# Power_and_Clocks.net
KiCad netlist of a schematic drawn in Altium Designer
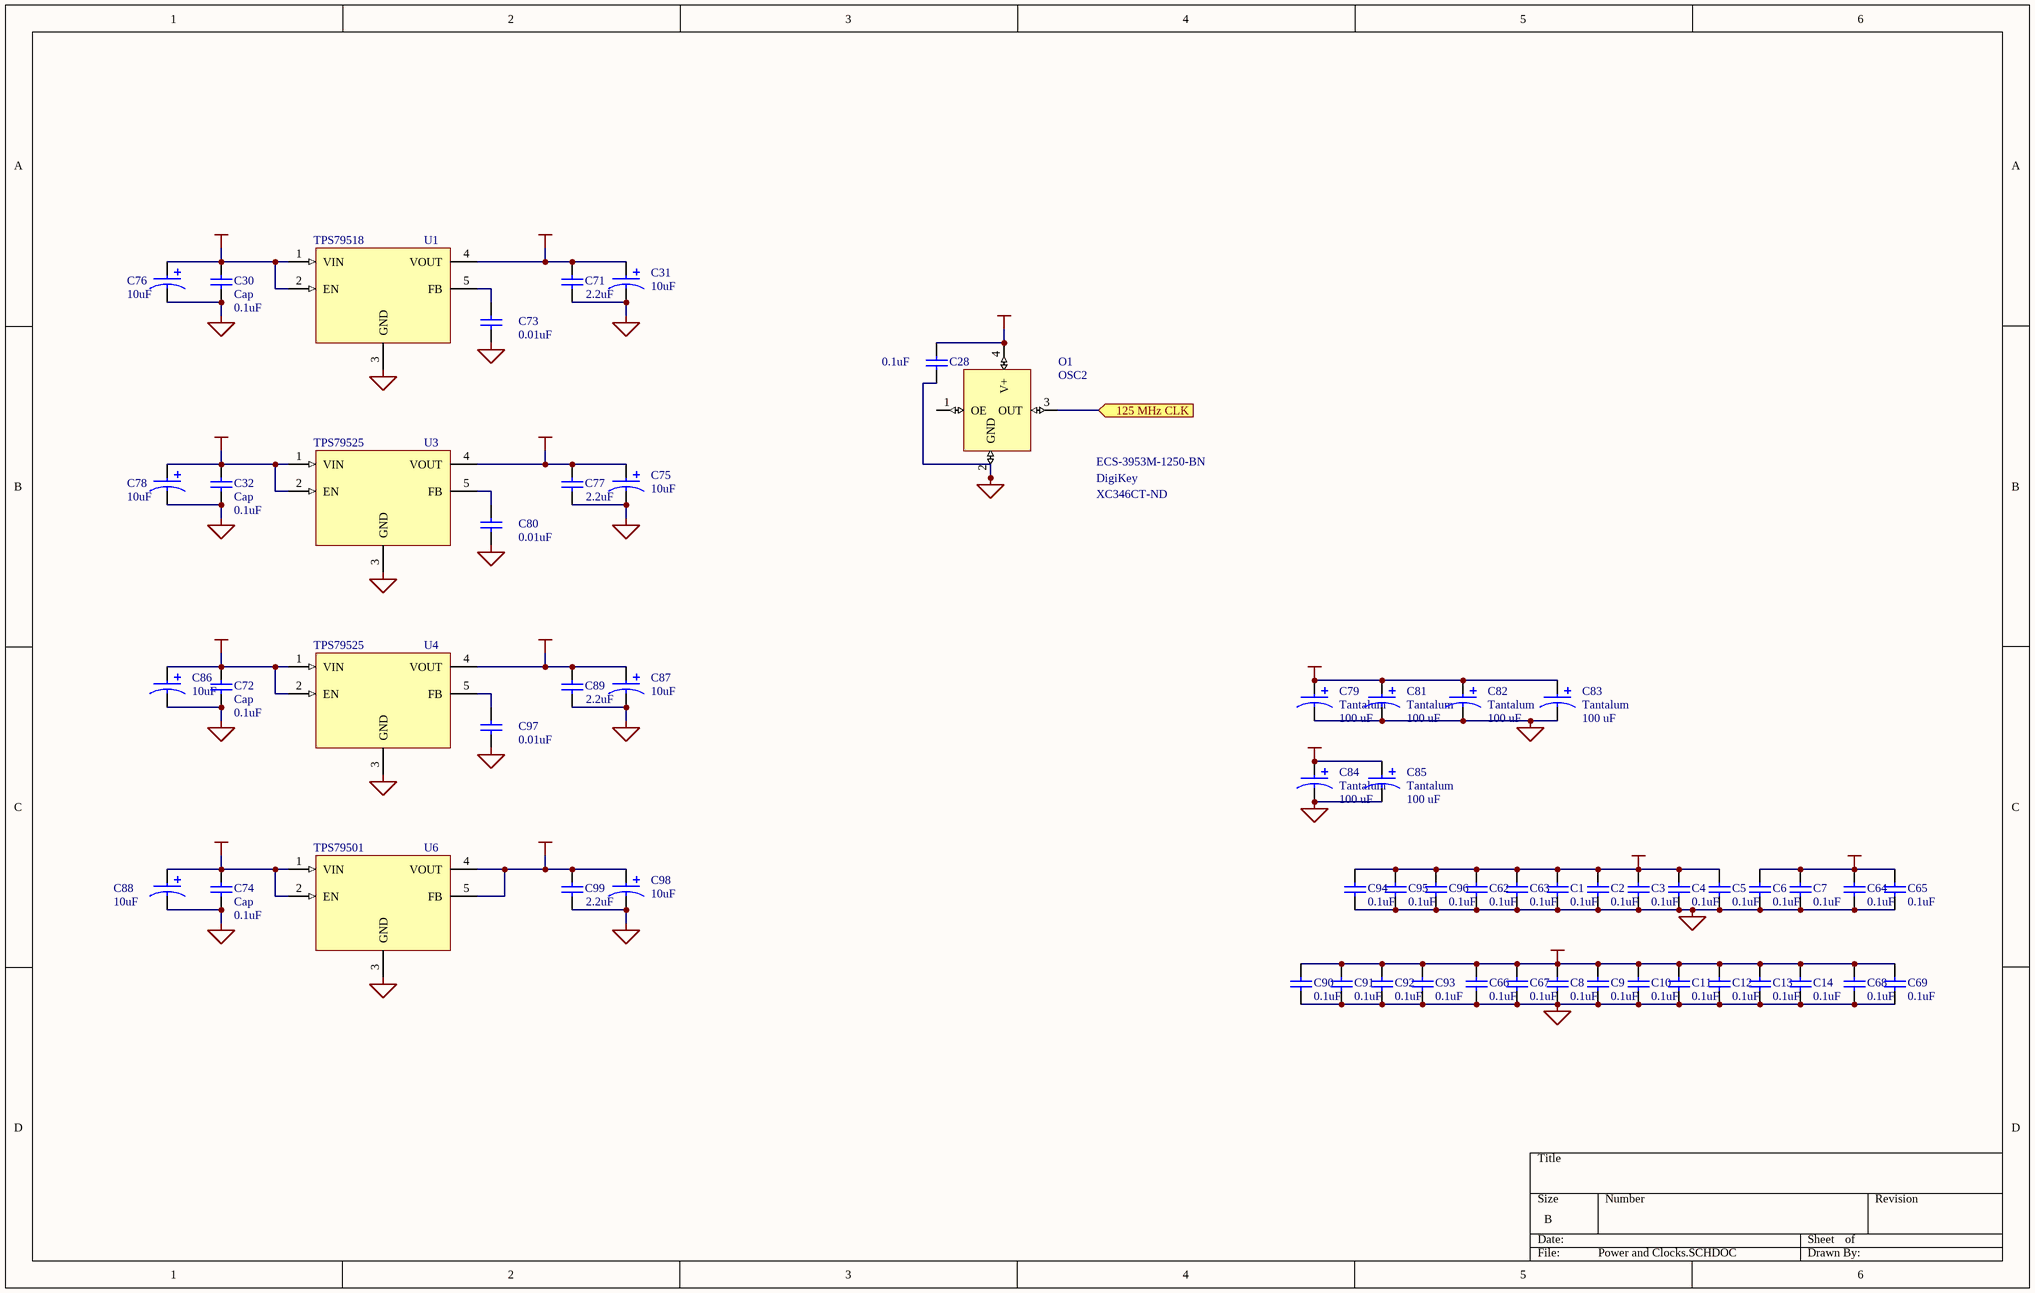
[diagram p0: Power and Clocks.SCHDOC]

(export (version "E")
  (design (tool "Eeschema 10.0.6"))
  (components
    (comp (ref "C1")
      (value "0.1uF")
      (footprint "0603")
      (description "Capacitor")
      (fields
        (field (name "MANUFACTURER") "Generic Components")
        (field (name "Comment") "Cap")
        (field (name "PUBLISHER") "Altium Limited")
      )
      (libsource (lib "Miscellaneous Devices") (part "Cap"))
    )
    (comp (ref "C2")
      (value "0.1uF")
      (footprint "0603")
      (description "Capacitor")
      (fields
        (field (name "MANUFACTURER") "Generic Components")
        (field (name "Comment") "Cap")
        (field (name "PUBLISHER") "Altium Limited")
      )
      (libsource (lib "Miscellaneous Devices") (part "Cap"))
    )
    (comp (ref "C3")
      (value "0.1uF")
      (footprint "0603")
      (description "Capacitor")
      (fields
        (field (name "MANUFACTURER") "Generic Components")
        (field (name "Comment") "Cap")
        (field (name "PUBLISHER") "Altium Limited")
      )
      (libsource (lib "Miscellaneous Devices") (part "Cap"))
    )
    (comp (ref "C4")
      (value "0.1uF")
      (footprint "0603")
      (description "Capacitor")
      (fields
        (field (name "MANUFACTURER") "Generic Components")
        (field (name "Comment") "Cap")
        (field (name "PUBLISHER") "Altium Limited")
      )
      (libsource (lib "Miscellaneous Devices") (part "Cap"))
    )
    (comp (ref "C5")
      (value "0.1uF")
      (footprint "0603")
      (description "Capacitor")
      (fields
        (field (name "MANUFACTURER") "Generic Components")
        (field (name "Comment") "Cap")
        (field (name "PUBLISHER") "Altium Limited")
      )
      (libsource (lib "Miscellaneous Devices") (part "Cap"))
    )
    (comp (ref "C6")
      (value "0.1uF")
      (footprint "0603")
      (description "Capacitor")
      (fields
        (field (name "MANUFACTURER") "Generic Components")
        (field (name "Comment") "Cap")
        (field (name "PUBLISHER") "Altium Limited")
      )
      (libsource (lib "Miscellaneous Devices") (part "Cap"))
    )
    (comp (ref "C7")
      (value "0.1uF")
      (footprint "0603")
      (description "Capacitor")
      (fields
        (field (name "MANUFACTURER") "Generic Components")
        (field (name "Comment") "Cap")
        (field (name "PUBLISHER") "Altium Limited")
      )
      (libsource (lib "Miscellaneous Devices") (part "Cap"))
    )
    (comp (ref "C8")
      (value "0.1uF")
      (footprint "0603")
      (description "Capacitor")
      (fields
        (field (name "MANUFACTURER") "Generic Components")
        (field (name "Comment") "Cap")
        (field (name "PUBLISHER") "Altium Limited")
      )
      (libsource (lib "Miscellaneous Devices") (part "Cap"))
    )
    (comp (ref "C9")
      (value "0.1uF")
      (footprint "0603")
      (description "Capacitor")
      (fields
        (field (name "MANUFACTURER") "Generic Components")
        (field (name "Comment") "Cap")
        (field (name "PUBLISHER") "Altium Limited")
      )
      (libsource (lib "Miscellaneous Devices") (part "Cap"))
    )
    (comp (ref "C10")
      (value "0.1uF")
      (footprint "0603")
      (description "Capacitor")
      (fields
        (field (name "MANUFACTURER") "Generic Components")
        (field (name "Comment") "Cap")
        (field (name "PUBLISHER") "Altium Limited")
      )
      (libsource (lib "Miscellaneous Devices") (part "Cap"))
    )
    (comp (ref "C11")
      (value "0.1uF")
      (footprint "0603")
      (description "Capacitor")
      (fields
        (field (name "MANUFACTURER") "Generic Components")
        (field (name "Comment") "Cap")
        (field (name "PUBLISHER") "Altium Limited")
      )
      (libsource (lib "Miscellaneous Devices") (part "Cap"))
    )
    (comp (ref "C12")
      (value "0.1uF")
      (footprint "0603")
      (description "Capacitor")
      (fields
        (field (name "MANUFACTURER") "Generic Components")
        (field (name "Comment") "Cap")
        (field (name "PUBLISHER") "Altium Limited")
      )
      (libsource (lib "Miscellaneous Devices") (part "Cap"))
    )
    (comp (ref "C13")
      (value "0.1uF")
      (footprint "0603")
      (description "Capacitor")
      (fields
        (field (name "MANUFACTURER") "Generic Components")
        (field (name "Comment") "Cap")
        (field (name "PUBLISHER") "Altium Limited")
      )
      (libsource (lib "Miscellaneous Devices") (part "Cap"))
    )
    (comp (ref "C14")
      (value "0.1uF")
      (footprint "0603")
      (description "Capacitor")
      (fields
        (field (name "MANUFACTURER") "Generic Components")
        (field (name "Comment") "Cap")
        (field (name "PUBLISHER") "Altium Limited")
      )
      (libsource (lib "Miscellaneous Devices") (part "Cap"))
    )
    (comp (ref "C28")
      (value "0.1uF")
      (footprint "CC1608-0603")
      (description "Capacitor")
      (fields
        (field (name "MANUFACTURER") "Generic Components")
        (field (name "Comment") "Cap")
        (field (name "PUBLISHER") "Altium Limited")
      )
      (libsource (lib "Miscellaneous Devices") (part "Cap"))
    )
    (comp (ref "C30")
      (value "Cap")
      (footprint "CC1608-0603")
      (description "Capacitor")
      (fields
        (field (name "MANUFACTURER") "Generic Components")
        (field (name "ALTIUM_VALUE") "0.1uF")
        (field (name "PUBLISHER") "Altium Limited")
      )
      (libsource (lib "Miscellaneous Devices") (part "Cap"))
    )
    (comp (ref "C31")
      (value "10uF")
      (footprint "6032")
      (description "Standard Capacitor")
      (fields (field (name "Comment") "POLCAP2"))
      (libsource (lib "parts") (part "POLCAP2"))
    )
    (comp (ref "C32")
      (value "Cap")
      (footprint "CC1608-0603")
      (description "Capacitor")
      (fields
        (field (name "MANUFACTURER") "Generic Components")
        (field (name "ALTIUM_VALUE") "0.1uF")
        (field (name "PUBLISHER") "Altium Limited")
      )
      (libsource (lib "Miscellaneous Devices") (part "Cap"))
    )
    (comp (ref "C62")
      (value "0.1uF")
      (footprint "0603")
      (description "Capacitor")
      (fields
        (field (name "MANUFACTURER") "Generic Components")
        (field (name "Comment") "Cap")
        (field (name "PUBLISHER") "Altium Limited")
      )
      (libsource (lib "Miscellaneous Devices") (part "Cap"))
    )
    (comp (ref "C63")
      (value "0.1uF")
      (footprint "0603")
      (description "Capacitor")
      (fields
        (field (name "MANUFACTURER") "Generic Components")
        (field (name "Comment") "Cap")
        (field (name "PUBLISHER") "Altium Limited")
      )
      (libsource (lib "Miscellaneous Devices") (part "Cap"))
    )
    (comp (ref "C64")
      (value "0.1uF")
      (footprint "0603")
      (description "Capacitor")
      (fields
        (field (name "MANUFACTURER") "Generic Components")
        (field (name "Comment") "Cap")
        (field (name "PUBLISHER") "Altium Limited")
      )
      (libsource (lib "Miscellaneous Devices") (part "Cap"))
    )
    (comp (ref "C65")
      (value "0.1uF")
      (footprint "0603")
      (description "Capacitor")
      (fields
        (field (name "MANUFACTURER") "Generic Components")
        (field (name "Comment") "Cap")
        (field (name "PUBLISHER") "Altium Limited")
      )
      (libsource (lib "Miscellaneous Devices") (part "Cap"))
    )
    (comp (ref "C66")
      (value "0.1uF")
      (footprint "0603")
      (description "Capacitor")
      (fields
        (field (name "MANUFACTURER") "Generic Components")
        (field (name "Comment") "Cap")
        (field (name "PUBLISHER") "Altium Limited")
      )
      (libsource (lib "Miscellaneous Devices") (part "Cap"))
    )
    (comp (ref "C67")
      (value "0.1uF")
      (footprint "0603")
      (description "Capacitor")
      (fields
        (field (name "MANUFACTURER") "Generic Components")
        (field (name "Comment") "Cap")
        (field (name "PUBLISHER") "Altium Limited")
      )
      (libsource (lib "Miscellaneous Devices") (part "Cap"))
    )
    (comp (ref "C68")
      (value "0.1uF")
      (footprint "0603")
      (description "Capacitor")
      (fields
        (field (name "MANUFACTURER") "Generic Components")
        (field (name "Comment") "Cap")
        (field (name "PUBLISHER") "Altium Limited")
      )
      (libsource (lib "Miscellaneous Devices") (part "Cap"))
    )
    (comp (ref "C69")
      (value "0.1uF")
      (footprint "0603")
      (description "Capacitor")
      (fields
        (field (name "MANUFACTURER") "Generic Components")
        (field (name "Comment") "Cap")
        (field (name "PUBLISHER") "Altium Limited")
      )
      (libsource (lib "Miscellaneous Devices") (part "Cap"))
    )
    (comp (ref "C71")
      (value "2.2uF")
      (footprint "1206")
      (description "Capacitor")
      (fields
        (field (name "MANUFACTURER") "Generic Components")
        (field (name "Comment") "Cap")
        (field (name "PUBLISHER") "Altium Limited")
      )
      (libsource (lib "Miscellaneous Devices") (part "Cap"))
    )
    (comp (ref "C72")
      (value "Cap")
      (footprint "CC1608-0603")
      (description "Capacitor")
      (fields
        (field (name "MANUFACTURER") "Generic Components")
        (field (name "ALTIUM_VALUE") "0.1uF")
        (field (name "PUBLISHER") "Altium Limited")
      )
      (libsource (lib "Miscellaneous Devices") (part "Cap"))
    )
    (comp (ref "C73")
      (value "0.01uF")
      (footprint "0603")
      (description "Capacitor")
      (fields
        (field (name "MANUFACTURER") "Generic Components")
        (field (name "Comment") "Cap")
        (field (name "PUBLISHER") "Altium Limited")
      )
      (libsource (lib "Miscellaneous Devices") (part "Cap"))
    )
    (comp (ref "C74")
      (value "Cap")
      (footprint "CC1608-0603")
      (description "Capacitor")
      (fields
        (field (name "MANUFACTURER") "Generic Components")
        (field (name "ALTIUM_VALUE") "0.1uF")
        (field (name "PUBLISHER") "Altium Limited")
      )
      (libsource (lib "Miscellaneous Devices") (part "Cap"))
    )
    (comp (ref "C75")
      (value "10uF")
      (footprint "6032")
      (description "Standard Capacitor")
      (fields (field (name "Comment") "POLCAP2"))
      (libsource (lib "parts") (part "POLCAP2"))
    )
    (comp (ref "C76")
      (value "10uF")
      (footprint "6032")
      (description "Standard Capacitor")
      (fields (field (name "Comment") "POLCAP2"))
      (libsource (lib "parts") (part "POLCAP2"))
    )
    (comp (ref "C77")
      (value "2.2uF")
      (footprint "1206")
      (description "Capacitor")
      (fields
        (field (name "MANUFACTURER") "Generic Components")
        (field (name "Comment") "Cap")
        (field (name "PUBLISHER") "Altium Limited")
      )
      (libsource (lib "Miscellaneous Devices") (part "Cap"))
    )
    (comp (ref "C78")
      (value "10uF")
      (footprint "6032")
      (description "Standard Capacitor")
      (fields (field (name "Comment") "POLCAP2"))
      (libsource (lib "parts") (part "POLCAP2"))
    )
    (comp (ref "C79")
      (value "Tantalum")
      (footprint "6032")
      (description "Standard Capacitor")
      (fields (field (name "ALTIUM_VALUE") "100 uF"))
      (libsource (lib "parts") (part "POLCAP2"))
    )
    (comp (ref "C80")
      (value "0.01uF")
      (footprint "0603")
      (description "Capacitor")
      (fields
        (field (name "MANUFACTURER") "Generic Components")
        (field (name "Comment") "Cap")
        (field (name "PUBLISHER") "Altium Limited")
      )
      (libsource (lib "Miscellaneous Devices") (part "Cap"))
    )
    (comp (ref "C81")
      (value "Tantalum")
      (footprint "6032")
      (description "Standard Capacitor")
      (fields (field (name "ALTIUM_VALUE") "100 uF"))
      (libsource (lib "parts") (part "POLCAP2"))
    )
    (comp (ref "C82")
      (value "Tantalum")
      (footprint "6032")
      (description "Standard Capacitor")
      (fields (field (name "ALTIUM_VALUE") "100 uF"))
      (libsource (lib "parts") (part "POLCAP2"))
    )
    (comp (ref "C83")
      (value "Tantalum")
      (footprint "6032")
      (description "Standard Capacitor")
      (fields (field (name "ALTIUM_VALUE") "100 uF"))
      (libsource (lib "parts") (part "POLCAP2"))
    )
    (comp (ref "C84")
      (value "Tantalum")
      (footprint "6032")
      (description "Standard Capacitor")
      (fields (field (name "ALTIUM_VALUE") "100 uF"))
      (libsource (lib "parts") (part "POLCAP2"))
    )
    (comp (ref "C85")
      (value "Tantalum")
      (footprint "6032")
      (description "Standard Capacitor")
      (fields (field (name "ALTIUM_VALUE") "100 uF"))
      (libsource (lib "parts") (part "POLCAP2"))
    )
    (comp (ref "C86")
      (value "10uF")
      (footprint "6032")
      (description "Standard Capacitor")
      (fields (field (name "Comment") "POLCAP2"))
      (libsource (lib "parts") (part "POLCAP2"))
    )
    (comp (ref "C87")
      (value "10uF")
      (footprint "6032")
      (description "Standard Capacitor")
      (fields (field (name "Comment") "POLCAP2"))
      (libsource (lib "parts") (part "POLCAP2"))
    )
    (comp (ref "C88")
      (value "10uF")
      (footprint "6032")
      (description "Standard Capacitor")
      (fields (field (name "Comment") "POLCAP2"))
      (libsource (lib "parts") (part "POLCAP2"))
    )
    (comp (ref "C89")
      (value "2.2uF")
      (footprint "1206")
      (description "Capacitor")
      (fields
        (field (name "MANUFACTURER") "Generic Components")
        (field (name "Comment") "Cap")
        (field (name "PUBLISHER") "Altium Limited")
      )
      (libsource (lib "Miscellaneous Devices") (part "Cap"))
    )
    (comp (ref "C90")
      (value "0.1uF")
      (footprint "0603")
      (description "Capacitor")
      (fields
        (field (name "MANUFACTURER") "Generic Components")
        (field (name "Comment") "Cap")
        (field (name "PUBLISHER") "Altium Limited")
      )
      (libsource (lib "Miscellaneous Devices") (part "Cap"))
    )
    (comp (ref "C91")
      (value "0.1uF")
      (footprint "0603")
      (description "Capacitor")
      (fields
        (field (name "MANUFACTURER") "Generic Components")
        (field (name "Comment") "Cap")
        (field (name "PUBLISHER") "Altium Limited")
      )
      (libsource (lib "Miscellaneous Devices") (part "Cap"))
    )
    (comp (ref "C92")
      (value "0.1uF")
      (footprint "0603")
      (description "Capacitor")
      (fields
        (field (name "MANUFACTURER") "Generic Components")
        (field (name "Comment") "Cap")
        (field (name "PUBLISHER") "Altium Limited")
      )
      (libsource (lib "Miscellaneous Devices") (part "Cap"))
    )
    (comp (ref "C93")
      (value "0.1uF")
      (footprint "0603")
      (description "Capacitor")
      (fields
        (field (name "MANUFACTURER") "Generic Components")
        (field (name "Comment") "Cap")
        (field (name "PUBLISHER") "Altium Limited")
      )
      (libsource (lib "Miscellaneous Devices") (part "Cap"))
    )
    (comp (ref "C94")
      (value "0.1uF")
      (footprint "0603")
      (description "Capacitor")
      (fields
        (field (name "MANUFACTURER") "Generic Components")
        (field (name "Comment") "Cap")
        (field (name "PUBLISHER") "Altium Limited")
      )
      (libsource (lib "Miscellaneous Devices") (part "Cap"))
    )
    (comp (ref "C95")
      (value "0.1uF")
      (footprint "0603")
      (description "Capacitor")
      (fields
        (field (name "MANUFACTURER") "Generic Components")
        (field (name "Comment") "Cap")
        (field (name "PUBLISHER") "Altium Limited")
      )
      (libsource (lib "Miscellaneous Devices") (part "Cap"))
    )
    (comp (ref "C96")
      (value "0.1uF")
      (footprint "0603")
      (description "Capacitor")
      (fields
        (field (name "MANUFACTURER") "Generic Components")
        (field (name "Comment") "Cap")
        (field (name "PUBLISHER") "Altium Limited")
      )
      (libsource (lib "Miscellaneous Devices") (part "Cap"))
    )
    (comp (ref "C97")
      (value "0.01uF")
      (footprint "0603")
      (description "Capacitor")
      (fields
        (field (name "MANUFACTURER") "Generic Components")
        (field (name "Comment") "Cap")
        (field (name "PUBLISHER") "Altium Limited")
      )
      (libsource (lib "Miscellaneous Devices") (part "Cap"))
    )
    (comp (ref "C98")
      (value "10uF")
      (footprint "6032")
      (description "Standard Capacitor")
      (fields (field (name "Comment") "POLCAP2"))
      (libsource (lib "parts") (part "POLCAP2"))
    )
    (comp (ref "C99")
      (value "2.2uF")
      (footprint "1206")
      (description "Capacitor")
      (fields
        (field (name "MANUFACTURER") "Generic Components")
        (field (name "Comment") "Cap")
        (field (name "PUBLISHER") "Altium Limited")
      )
      (libsource (lib "Miscellaneous Devices") (part "Cap"))
    )
    (comp (ref "O1")
      (value "OSC2")
      (footprint "ECS-3953M")
      (description "ECS SMD Oscillator, ECS-3953M")
      (fields
        (field (name "PART") "ECS-3953M-1250-BN")
        (field (name "VENDOR") "DigiKey")
        (field (name "VENDORPART") "XC346CT-ND")
      )
      (libsource (lib "My devices") (part "OSC2"))
    )
    (comp (ref "U1")
      (value "TPS79518")
      (footprint "SOT223-5/Simple")
      (description "TI Ultra-low-noise LDO")
      (libsource (lib "parts") (part "TPS795XX"))
    )
    (comp (ref "U3")
      (value "TPS79525")
      (footprint "SOT223-5/Simple")
      (description "TI Ultra-low-noise LDO")
      (libsource (lib "parts") (part "TPS795XX"))
    )
    (comp (ref "U4")
      (value "TPS79525")
      (footprint "SOT223-5/Simple")
      (description "TI Ultra-low-noise LDO")
      (libsource (lib "parts") (part "TPS795XX"))
    )
    (comp (ref "U6")
      (value "TPS79501")
      (footprint "SOT223-5/Simple")
      (description "TI Ultra-low-noise LDO")
      (libsource (lib "parts") (part "TPS795XX"))
    )
  )
  (nets
    (net (code "1") (name "+1.2VCC") (class "Default")
      (node (ref "C6") (pin "2") (pinfunction "2_2") (pintype "passive"))
      (node (ref "C64") (pin "2") (pinfunction "2_2") (pintype "passive"))
      (node (ref "C65") (pin "2") (pinfunction "2_2") (pintype "passive"))
      (node (ref "C7") (pin "2") (pinfunction "2_2") (pintype "passive"))
      (node (ref "C98") (pin "1") (pintype "passive"))
      (node (ref "C99") (pin "2") (pinfunction "2_2") (pintype "passive"))
      (node (ref "U6") (pin "4") (pinfunction "VOUT_4") (pintype "power_in"))
      (node (ref "U6") (pin "5") (pinfunction "FB_5") (pintype "passive"))
    )
    (net (code "2") (name "+1.8VCC") (class "Default")
      (node (ref "C31") (pin "1") (pintype "passive"))
      (node (ref "C71") (pin "2") (pinfunction "2_2") (pintype "passive"))
      (node (ref "C84") (pin "1") (pintype "passive"))
      (node (ref "C85") (pin "1") (pintype "passive"))
      (node (ref "U1") (pin "4") (pinfunction "VOUT_4") (pintype "power_in"))
    )
    (net (code "3") (name "+2.5VCC") (class "Default")
      (node (ref "C1") (pin "2") (pinfunction "2_2") (pintype "passive"))
      (node (ref "C2") (pin "2") (pinfunction "2_2") (pintype "passive"))
      (node (ref "C3") (pin "2") (pinfunction "2_2") (pintype "passive"))
      (node (ref "C4") (pin "2") (pinfunction "2_2") (pintype "passive"))
      (node (ref "C5") (pin "2") (pinfunction "2_2") (pintype "passive"))
      (node (ref "C62") (pin "2") (pinfunction "2_2") (pintype "passive"))
      (node (ref "C63") (pin "2") (pinfunction "2_2") (pintype "passive"))
      (node (ref "C75") (pin "1") (pintype "passive"))
      (node (ref "C77") (pin "2") (pinfunction "2_2") (pintype "passive"))
      (node (ref "C94") (pin "2") (pinfunction "2_2") (pintype "passive"))
      (node (ref "C95") (pin "2") (pinfunction "2_2") (pintype "passive"))
      (node (ref "C96") (pin "2") (pinfunction "2_2") (pintype "passive"))
      (node (ref "U3") (pin "4") (pinfunction "VOUT_4") (pintype "power_in"))
    )
    (net (code "4") (name "+2.5VPHY") (class "Default")
      (node (ref "C87") (pin "1") (pintype "passive"))
      (node (ref "C89") (pin "2") (pinfunction "2_2") (pintype "passive"))
      (node (ref "U4") (pin "4") (pinfunction "VOUT_4") (pintype "power_in"))
    )
    (net (code "5") (name "/125 MHz CLK") (class "Default")
      (node (ref "O1") (pin "3") (pinfunction "OUT_3") (pintype "bidirectional"))
    )
    (net (code "6") (name "GND") (class "Default")
      (node (ref "C1") (pin "1") (pinfunction "1_1") (pintype "passive"))
      (node (ref "C10") (pin "1") (pinfunction "1_1") (pintype "passive"))
      (node (ref "C11") (pin "1") (pinfunction "1_1") (pintype "passive"))
      (node (ref "C12") (pin "1") (pinfunction "1_1") (pintype "passive"))
      (node (ref "C13") (pin "1") (pinfunction "1_1") (pintype "passive"))
      (node (ref "C14") (pin "1") (pinfunction "1_1") (pintype "passive"))
      (node (ref "C2") (pin "1") (pinfunction "1_1") (pintype "passive"))
      (node (ref "C28") (pin "1") (pinfunction "1_1") (pintype "passive"))
      (node (ref "C3") (pin "1") (pinfunction "1_1") (pintype "passive"))
      (node (ref "C30") (pin "1") (pinfunction "1_1") (pintype "passive"))
      (node (ref "C31") (pin "2") (pintype "passive"))
      (node (ref "C32") (pin "1") (pinfunction "1_1") (pintype "passive"))
      (node (ref "C4") (pin "1") (pinfunction "1_1") (pintype "passive"))
      (node (ref "C5") (pin "1") (pinfunction "1_1") (pintype "passive"))
      (node (ref "C6") (pin "1") (pinfunction "1_1") (pintype "passive"))
      (node (ref "C62") (pin "1") (pinfunction "1_1") (pintype "passive"))
      (node (ref "C63") (pin "1") (pinfunction "1_1") (pintype "passive"))
      (node (ref "C64") (pin "1") (pinfunction "1_1") (pintype "passive"))
      (node (ref "C65") (pin "1") (pinfunction "1_1") (pintype "passive"))
      (node (ref "C66") (pin "1") (pinfunction "1_1") (pintype "passive"))
      (node (ref "C67") (pin "1") (pinfunction "1_1") (pintype "passive"))
      (node (ref "C68") (pin "1") (pinfunction "1_1") (pintype "passive"))
      (node (ref "C69") (pin "1") (pinfunction "1_1") (pintype "passive"))
      (node (ref "C7") (pin "1") (pinfunction "1_1") (pintype "passive"))
      (node (ref "C71") (pin "1") (pinfunction "1_1") (pintype "passive"))
      (node (ref "C72") (pin "1") (pinfunction "1_1") (pintype "passive"))
      (node (ref "C73") (pin "1") (pinfunction "1_1") (pintype "passive"))
      (node (ref "C74") (pin "1") (pinfunction "1_1") (pintype "passive"))
      (node (ref "C75") (pin "2") (pintype "passive"))
      (node (ref "C76") (pin "2") (pintype "passive"))
      (node (ref "C77") (pin "1") (pinfunction "1_1") (pintype "passive"))
      (node (ref "C78") (pin "2") (pintype "passive"))
      (node (ref "C79") (pin "2") (pintype "passive"))
      (node (ref "C8") (pin "1") (pinfunction "1_1") (pintype "passive"))
      (node (ref "C80") (pin "1") (pinfunction "1_1") (pintype "passive"))
      (node (ref "C81") (pin "2") (pintype "passive"))
      (node (ref "C82") (pin "2") (pintype "passive"))
      (node (ref "C83") (pin "2") (pintype "passive"))
      (node (ref "C84") (pin "2") (pintype "passive"))
      (node (ref "C85") (pin "2") (pintype "passive"))
      (node (ref "C86") (pin "2") (pintype "passive"))
      (node (ref "C87") (pin "2") (pintype "passive"))
      (node (ref "C88") (pin "2") (pintype "passive"))
      (node (ref "C89") (pin "1") (pinfunction "1_1") (pintype "passive"))
      (node (ref "C9") (pin "1") (pinfunction "1_1") (pintype "passive"))
      (node (ref "C90") (pin "1") (pinfunction "1_1") (pintype "passive"))
      (node (ref "C91") (pin "1") (pinfunction "1_1") (pintype "passive"))
      (node (ref "C92") (pin "1") (pinfunction "1_1") (pintype "passive"))
      (node (ref "C93") (pin "1") (pinfunction "1_1") (pintype "passive"))
      (node (ref "C94") (pin "1") (pinfunction "1_1") (pintype "passive"))
      (node (ref "C95") (pin "1") (pinfunction "1_1") (pintype "passive"))
      (node (ref "C96") (pin "1") (pinfunction "1_1") (pintype "passive"))
      (node (ref "C97") (pin "1") (pinfunction "1_1") (pintype "passive"))
      (node (ref "C98") (pin "2") (pintype "passive"))
      (node (ref "C99") (pin "1") (pinfunction "1_1") (pintype "passive"))
      (node (ref "O1") (pin "2") (pinfunction "GND_2") (pintype "bidirectional"))
      (node (ref "U1") (pin "3") (pinfunction "GND_3") (pintype "power_in"))
      (node (ref "U3") (pin "3") (pinfunction "GND_3") (pintype "power_in"))
      (node (ref "U4") (pin "3") (pinfunction "GND_3") (pintype "power_in"))
      (node (ref "U6") (pin "3") (pinfunction "GND_3") (pintype "power_in"))
    )
    (net (code "7") (name "Net-(U1-FB)") (class "Default")
      (node (ref "C73") (pin "2") (pinfunction "2_2") (pintype "passive"))
      (node (ref "U1") (pin "5") (pinfunction "FB_5") (pintype "passive"))
    )
    (net (code "8") (name "Net-(U3-FB)") (class "Default")
      (node (ref "C80") (pin "2") (pinfunction "2_2") (pintype "passive"))
      (node (ref "U3") (pin "5") (pinfunction "FB_5") (pintype "passive"))
    )
    (net (code "9") (name "Net-(U4-FB)") (class "Default")
      (node (ref "C97") (pin "2") (pinfunction "2_2") (pintype "passive"))
      (node (ref "U4") (pin "5") (pinfunction "FB_5") (pintype "passive"))
    )
    (net (code "10") (name "VCC") (class "Default")
      (node (ref "C10") (pin "2") (pinfunction "2_2") (pintype "passive"))
      (node (ref "C11") (pin "2") (pinfunction "2_2") (pintype "passive"))
      (node (ref "C12") (pin "2") (pinfunction "2_2") (pintype "passive"))
      (node (ref "C13") (pin "2") (pinfunction "2_2") (pintype "passive"))
      (node (ref "C14") (pin "2") (pinfunction "2_2") (pintype "passive"))
      (node (ref "C28") (pin "2") (pinfunction "2_2") (pintype "passive"))
      (node (ref "C30") (pin "2") (pinfunction "2_2") (pintype "passive"))
      (node (ref "C32") (pin "2") (pinfunction "2_2") (pintype "passive"))
      (node (ref "C66") (pin "2") (pinfunction "2_2") (pintype "passive"))
      (node (ref "C67") (pin "2") (pinfunction "2_2") (pintype "passive"))
      (node (ref "C68") (pin "2") (pinfunction "2_2") (pintype "passive"))
      (node (ref "C69") (pin "2") (pinfunction "2_2") (pintype "passive"))
      (node (ref "C72") (pin "2") (pinfunction "2_2") (pintype "passive"))
      (node (ref "C74") (pin "2") (pinfunction "2_2") (pintype "passive"))
      (node (ref "C76") (pin "1") (pintype "passive"))
      (node (ref "C78") (pin "1") (pintype "passive"))
      (node (ref "C79") (pin "1") (pintype "passive"))
      (node (ref "C8") (pin "2") (pinfunction "2_2") (pintype "passive"))
      (node (ref "C81") (pin "1") (pintype "passive"))
      (node (ref "C82") (pin "1") (pintype "passive"))
      (node (ref "C83") (pin "1") (pintype "passive"))
      (node (ref "C86") (pin "1") (pintype "passive"))
      (node (ref "C88") (pin "1") (pintype "passive"))
      (node (ref "C9") (pin "2") (pinfunction "2_2") (pintype "passive"))
      (node (ref "C90") (pin "2") (pinfunction "2_2") (pintype "passive"))
      (node (ref "C91") (pin "2") (pinfunction "2_2") (pintype "passive"))
      (node (ref "C92") (pin "2") (pinfunction "2_2") (pintype "passive"))
      (node (ref "C93") (pin "2") (pinfunction "2_2") (pintype "passive"))
      (node (ref "O1") (pin "4") (pinfunction "V+_4") (pintype "bidirectional"))
      (node (ref "U1") (pin "1") (pinfunction "VIN_1") (pintype "input"))
      (node (ref "U1") (pin "2") (pinfunction "EN_2") (pintype "input"))
      (node (ref "U3") (pin "1") (pinfunction "VIN_1") (pintype "input"))
      (node (ref "U3") (pin "2") (pinfunction "EN_2") (pintype "input"))
      (node (ref "U4") (pin "1") (pinfunction "VIN_1") (pintype "input"))
      (node (ref "U4") (pin "2") (pinfunction "EN_2") (pintype "input"))
      (node (ref "U6") (pin "1") (pinfunction "VIN_1") (pintype "input"))
      (node (ref "U6") (pin "2") (pinfunction "EN_2") (pintype "input"))
    )
    (net (code "11") (name "unconnected-(O1-OE-Pad1)") (class "Default")
      (node (ref "O1") (pin "1") (pinfunction "OE_1") (pintype "bidirectional"))
    )
  )
)
